# FPGA_USB.net
KiCad netlist of a schematic drawn in Altium Designer
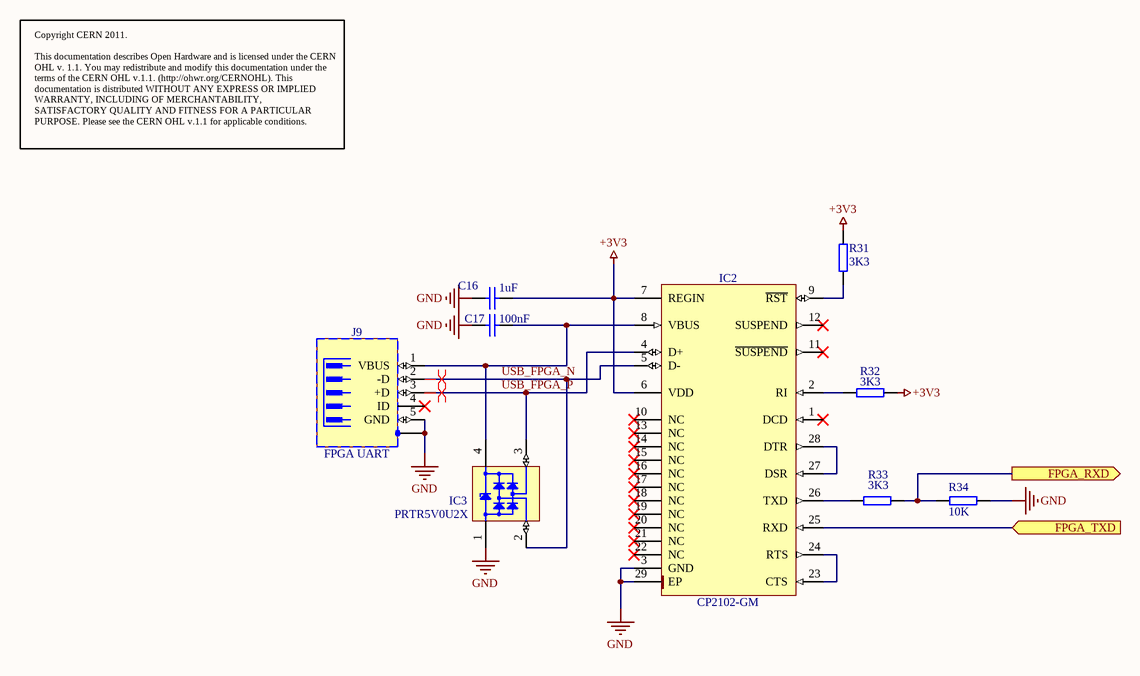
[diagram p0: FPGA_USB.SchDoc]

(export (version "E")
  (design (tool "Eeschema 10.0.6"))
  (components
    (comp (ref "C16")
      (value "1uF")
      (footprint "CC1608-0603")
      (description "Capacitor")
      (fields
        (field (name "TOLERANCE") "±10%")
        (field (name "VOLTAGE") "25V")
        (field (name "PUBLISHER") "Altium Limited")
      )
      (libsource (lib "wr_switch") (part "Cap"))
    )
    (comp (ref "C17")
      (value "100nF")
      (footprint "CC1608-0603")
      (description "Capacitor")
      (fields
        (field (name "TOLERANCE") "±10%")
        (field (name "VOLTAGE") "16V")
        (field (name "PUBLISHER") "Altium Limited")
      )
      (libsource (lib "wr_switch") (part "Cap"))
    )
    (comp (ref "IC2")
      (value "CP2102-GM")
      (footprint "7S_WR:QFN50P500X500X100-29N-S335")
      (description "Single-Chip USB to UART Bridge")
      (fields (field (name "MANUFACTURER") "SILICON LABS") (field (name "AUTHOR") "CERN DEM JLC"))
      (libsource (lib "wr_switch") (part "CP2102-GM"))
    )
    (comp (ref "IC3")
      (value "PRTR5V0U2X")
      (footprint "7S_WR:SOT190P230X110-4N")
      (description "Ultra Low Capacitance Double Rail-to-Rail ESD Protection Diode")
      (fields
        (field (name "VOLTAGE") "5.5V")
        (field (name "MANUFACTURER") "PHILIPS NXP")
        (field (name "AUTHOR") "CERN DEM JLC")
      )
      (libsource (lib "wr_switch") (part "PRTR5V0U2X"))
    )
    (comp (ref "J9")
      (value "FPGA UART")
      (footprint "7S_WR:TYCO_1734035-1")
      (description "5 Pin + 1 Shield Mini USB Type B Receptacle")
      (fields
        (field (name "PART NUMBER") "TYCO_1734035-1")
        (field (name "MANUFACTURER") "TYCO ELECTRONICS")
        (field (name "AUTHOR") "CERN DEM JLC")
      )
      (libsource (lib "wr_switch") (part "TYCO_1734035-1"))
    )
    (comp (ref "R31")
      (value "3K3")
      (footprint "0603")
      (description "SMD Resistor")
      (fields (field (name "TOLERANCE") "±1%"))
      (libsource (lib "wr_switch") (part "RES_SMD"))
    )
    (comp (ref "R32")
      (value "3K3")
      (footprint "0603")
      (description "SMD Resistor")
      (fields (field (name "TOLERANCE") "±1%"))
      (libsource (lib "wr_switch") (part "RES_SMD"))
    )
    (comp (ref "R33")
      (value "3K3")
      (footprint "0603")
      (description "SMD Resistor")
      (fields (field (name "TOLERANCE") "±1%"))
      (libsource (lib "wr_switch") (part "RES_SMD"))
    )
    (comp (ref "R34")
      (value "10K")
      (footprint "0603")
      (description "SMD Resistor")
      (fields (field (name "TOLERANCE") "±1%"))
      (libsource (lib "wr_switch") (part "RES_SMD"))
    )
  )
  (nets
    (net (code "1") (name "+3V3") (class "Default")
      (node (ref "C16") (pin "2") (pinfunction "2_2") (pintype "passive"))
      (node (ref "IC2") (pin "6") (pinfunction "VDD_6") (pintype "power_in"))
      (node (ref "IC2") (pin "7") (pinfunction "REGIN_7") (pintype "power_in"))
      (node (ref "R31") (pin "2") (pinfunction "2_2") (pintype "passive"))
      (node (ref "R32") (pin "2") (pinfunction "2_2") (pintype "passive"))
    )
    (net (code "2") (name "/FPGA_RXD") (class "Default")
      (node (ref "R33") (pin "2") (pinfunction "2_2") (pintype "passive"))
      (node (ref "R34") (pin "2") (pinfunction "2_2") (pintype "passive"))
    )
    (net (code "3") (name "/FPGA_TXD") (class "Default")
      (node (ref "IC2") (pin "25") (pinfunction "RXD_25") (pintype "input"))
    )
    (net (code "4") (name "/USB_FPGA_N") (class "Default")
      (node (ref "IC2") (pin "5") (pinfunction "D-_5") (pintype "bidirectional"))
      (node (ref "IC3") (pin "2") (pinfunction "I/O1_2") (pintype "bidirectional"))
      (node (ref "J9") (pin "2") (pinfunction "-D_2") (pintype "bidirectional"))
    )
    (net (code "5") (name "/USB_FPGA_P") (class "Default")
      (node (ref "IC2") (pin "4") (pinfunction "D+_4") (pintype "bidirectional"))
      (node (ref "IC3") (pin "3") (pinfunction "I/O2_3") (pintype "bidirectional"))
      (node (ref "J9") (pin "3") (pinfunction "+D_3") (pintype "bidirectional"))
    )
    (net (code "6") (name "GND") (class "Default")
      (node (ref "C16") (pin "1") (pinfunction "1_1") (pintype "passive"))
      (node (ref "C17") (pin "2") (pinfunction "2_2") (pintype "passive"))
      (node (ref "IC2") (pin "29") (pinfunction "EP_29") (pintype "power_in"))
      (node (ref "IC2") (pin "3") (pinfunction "GND_3") (pintype "power_in"))
      (node (ref "IC3") (pin "1") (pinfunction "GND_1") (pintype "power_in"))
      (node (ref "J9") (pin "5") (pinfunction "GND_5") (pintype "bidirectional"))
      (node (ref "J9") (pin "6") (pinfunction "SH_6") (pintype "power_in"))
      (node (ref "R34") (pin "1") (pinfunction "1_1") (pintype "passive"))
    )
    (net (code "7") (name "Net-(IC2-CTS)") (class "Default")
      (node (ref "IC2") (pin "23") (pinfunction "CTS_23") (pintype "input"))
      (node (ref "IC2") (pin "24") (pinfunction "RTS_24") (pintype "output"))
    )
    (net (code "8") (name "Net-(IC2-DSR)") (class "Default")
      (node (ref "IC2") (pin "27") (pinfunction "DSR_27") (pintype "input"))
      (node (ref "IC2") (pin "28") (pinfunction "DTR_28") (pintype "output"))
    )
    (net (code "9") (name "Net-(IC2-RI)") (class "Default")
      (node (ref "IC2") (pin "2") (pinfunction "RI_2") (pintype "input"))
      (node (ref "R32") (pin "1") (pinfunction "1_1") (pintype "passive"))
    )
    (net (code "10") (name "Net-(IC2-TXD)") (class "Default")
      (node (ref "IC2") (pin "26") (pinfunction "TXD_26") (pintype "output"))
      (node (ref "R33") (pin "1") (pinfunction "1_1") (pintype "passive"))
    )
    (net (code "11") (name "Net-(IC2-VBUS)") (class "Default")
      (node (ref "C17") (pin "1") (pinfunction "1_1") (pintype "passive"))
      (node (ref "IC2") (pin "8") (pinfunction "VBUS_8") (pintype "input"))
      (node (ref "IC3") (pin "4") (pinfunction "VCC_4") (pintype "power_in"))
      (node (ref "J9") (pin "1") (pinfunction "VBUS_1") (pintype "bidirectional"))
    )
    (net (code "12") (name "Net-(IC2-~{RST})") (class "Default")
      (node (ref "IC2") (pin "9") (pinfunction "~{RST}_9") (pintype "bidirectional"))
      (node (ref "R31") (pin "1") (pinfunction "1_1") (pintype "passive"))
    )
    (net (code "13") (name "unconnected-(IC2-DCD-Pad1)") (class "Default")
      (node (ref "IC2") (pin "1") (pinfunction "DCD_1") (pintype "input+no_connect"))
    )
    (net (code "14") (name "unconnected-(IC2-NC-Pad10)") (class "Default")
      (node (ref "IC2") (pin "10") (pinfunction "NC_10") (pintype "passive+no_connect"))
    )
    (net (code "15") (name "unconnected-(IC2-NC-Pad13)") (class "Default")
      (node (ref "IC2") (pin "13") (pinfunction "NC_13") (pintype "passive+no_connect"))
    )
    (net (code "16") (name "unconnected-(IC2-NC-Pad14)") (class "Default")
      (node (ref "IC2") (pin "14") (pinfunction "NC_14") (pintype "passive+no_connect"))
    )
    (net (code "17") (name "unconnected-(IC2-NC-Pad15)") (class "Default")
      (node (ref "IC2") (pin "15") (pinfunction "NC_15") (pintype "passive+no_connect"))
    )
    (net (code "18") (name "unconnected-(IC2-NC-Pad16)") (class "Default")
      (node (ref "IC2") (pin "16") (pinfunction "NC_16") (pintype "passive+no_connect"))
    )
    (net (code "19") (name "unconnected-(IC2-NC-Pad17)") (class "Default")
      (node (ref "IC2") (pin "17") (pinfunction "NC_17") (pintype "passive+no_connect"))
    )
    (net (code "20") (name "unconnected-(IC2-NC-Pad18)") (class "Default")
      (node (ref "IC2") (pin "18") (pinfunction "NC_18") (pintype "passive+no_connect"))
    )
    (net (code "21") (name "unconnected-(IC2-NC-Pad19)") (class "Default")
      (node (ref "IC2") (pin "19") (pinfunction "NC_19") (pintype "passive+no_connect"))
    )
    (net (code "22") (name "unconnected-(IC2-NC-Pad20)") (class "Default")
      (node (ref "IC2") (pin "20") (pinfunction "NC_20") (pintype "passive+no_connect"))
    )
    (net (code "23") (name "unconnected-(IC2-NC-Pad21)") (class "Default")
      (node (ref "IC2") (pin "21") (pinfunction "NC_21") (pintype "passive+no_connect"))
    )
    (net (code "24") (name "unconnected-(IC2-NC-Pad22)") (class "Default")
      (node (ref "IC2") (pin "22") (pinfunction "NC_22") (pintype "passive+no_connect"))
    )
    (net (code "25") (name "unconnected-(IC2-SUSPEND-Pad12)") (class "Default")
      (node (ref "IC2") (pin "12") (pinfunction "SUSPEND_12") (pintype "output+no_connect"))
    )
    (net (code "26") (name "unconnected-(IC2-~{SUSPEND}-Pad11)") (class "Default")
      (node (ref "IC2") (pin "11") (pinfunction "~{SUSPEND}_11") (pintype "output+no_connect"))
    )
    (net (code "27") (name "unconnected-(J9-ID-Pad4)") (class "Default")
      (node (ref "J9") (pin "4") (pinfunction "ID_4") (pintype "passive+no_connect"))
    )
  )
)
